# schematic.net
KiCad netlist of a schematic drawn in EAGLE
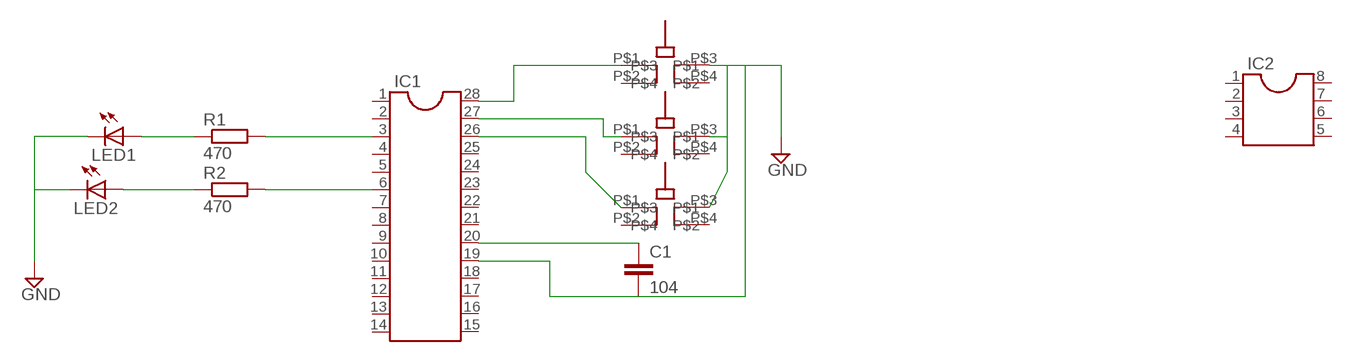
[diagram p0: schematic, sheet 1]

(export (version "E")
  (design (tool "Eeschema 10.0.6"))
  (components
    (comp (ref "C1")
      (value "104")
      (footprint "eagle-import:C2.5-5")
      (libsource (lib "eagle-import") (part "C2.5/5"))
    )
    (comp (ref "IC1")
      (value "DIL28-3")
      (footprint "eagle-import:DIL28-3")
      (libsource (lib "eagle-import") (part "DIL28-3"))
    )
    (comp (ref "IC2")
      (value "DIL8")
      (footprint "eagle-import:DIL08")
      (libsource (lib "eagle-import") (part "DIL8"))
    )
    (comp (ref "LED1")
      (value "LED3MM")
      (footprint "eagle-import:LED3MM")
      (libsource (lib "eagle-import") (part "LED3MM"))
    )
    (comp (ref "LED2")
      (value "LED3MM")
      (footprint "eagle-import:LED3MM")
      (libsource (lib "eagle-import") (part "LED3MM"))
    )
    (comp (ref "R1")
      (value "470")
      (footprint "eagle-import:0204_7")
      (libsource (lib "eagle-import") (part "R-EU_0204/7"))
    )
    (comp (ref "R2")
      (value "470")
      (footprint "eagle-import:0204_7")
      (libsource (lib "eagle-import") (part "R-EU_0204/7"))
    )
    (comp (ref "SW3")
      (value "KS4B")
      (footprint "eagle-import:KS4B")
      (libsource (lib "eagle-import") (part "KS4B"))
    )
    (comp (ref "U$1")
      (value "KS4B")
      (footprint "eagle-import:KS4B")
      (libsource (lib "eagle-import") (part "KS4B"))
    )
    (comp (ref "U$2")
      (value "KS4B")
      (footprint "eagle-import:KS4B")
      (libsource (lib "eagle-import") (part "KS4B"))
    )
  )
  (nets
    (net (code "1") (name "GND") (class "Default")
      (node (ref "C1") (pin "2") (pinfunction "2_2") (pintype "passive"))
      (node (ref "IC1") (pin "19") (pinfunction "19_19") (pintype "passive"))
      (node (ref "LED1") (pin "K") (pinfunction "C_K") (pintype "passive"))
      (node (ref "LED2") (pin "K") (pinfunction "C_K") (pintype "passive"))
      (node (ref "SW3") (pin "P$3") (pinfunction "P$3_P$3") (pintype "bidirectional"))
      (node (ref "U$1") (pin "P$3") (pinfunction "P$3_P$3") (pintype "bidirectional"))
      (node (ref "U$2") (pin "P$3") (pinfunction "P$3_P$3") (pintype "bidirectional"))
    )
    (net (code "2") (name "Net-(C1-Pad1)") (class "Default")
      (node (ref "C1") (pin "1") (pinfunction "1_1") (pintype "passive"))
      (node (ref "IC1") (pin "20") (pinfunction "20_20") (pintype "passive"))
    )
    (net (code "3") (name "Net-(IC1-Pad3)") (class "Default")
      (node (ref "IC1") (pin "3") (pinfunction "3_3") (pintype "passive"))
      (node (ref "R1") (pin "2") (pinfunction "2_2") (pintype "passive"))
    )
    (net (code "4") (name "Net-(IC1-Pad6)") (class "Default")
      (node (ref "IC1") (pin "6") (pinfunction "6_6") (pintype "passive"))
      (node (ref "R2") (pin "2") (pinfunction "2_2") (pintype "passive"))
    )
    (net (code "5") (name "Net-(IC1-Pad26)") (class "Default")
      (node (ref "IC1") (pin "26") (pinfunction "26_26") (pintype "passive"))
      (node (ref "SW3") (pin "P$1") (pinfunction "P$1_P$1") (pintype "bidirectional"))
    )
    (net (code "6") (name "Net-(IC1-Pad27)") (class "Default")
      (node (ref "IC1") (pin "27") (pinfunction "27_27") (pintype "passive"))
      (node (ref "U$2") (pin "P$1") (pinfunction "P$1_P$1") (pintype "bidirectional"))
    )
    (net (code "7") (name "Net-(IC1-Pad28)") (class "Default")
      (node (ref "IC1") (pin "28") (pinfunction "28_28") (pintype "passive"))
      (node (ref "U$1") (pin "P$1") (pinfunction "P$1_P$1") (pintype "bidirectional"))
    )
    (net (code "8") (name "Net-(LED1-PadA)") (class "Default")
      (node (ref "LED1") (pin "A") (pinfunction "A_A") (pintype "passive"))
      (node (ref "R1") (pin "1") (pinfunction "1_1") (pintype "passive"))
    )
    (net (code "9") (name "Net-(LED2-PadA)") (class "Default")
      (node (ref "LED2") (pin "A") (pinfunction "A_A") (pintype "passive"))
      (node (ref "R2") (pin "1") (pinfunction "1_1") (pintype "passive"))
    )
    (net (code "10") (name "unconnected-(IC1-Pad1)") (class "Default")
      (node (ref "IC1") (pin "1") (pinfunction "1_1") (pintype "passive"))
    )
    (net (code "11") (name "unconnected-(IC1-Pad2)") (class "Default")
      (node (ref "IC1") (pin "2") (pinfunction "2_2") (pintype "passive"))
    )
    (net (code "12") (name "unconnected-(IC1-Pad4)") (class "Default")
      (node (ref "IC1") (pin "4") (pinfunction "4_4") (pintype "passive"))
    )
    (net (code "13") (name "unconnected-(IC1-Pad5)") (class "Default")
      (node (ref "IC1") (pin "5") (pinfunction "5_5") (pintype "passive"))
    )
    (net (code "14") (name "unconnected-(IC1-Pad7)") (class "Default")
      (node (ref "IC1") (pin "7") (pinfunction "7_7") (pintype "passive"))
    )
    (net (code "15") (name "unconnected-(IC1-Pad8)") (class "Default")
      (node (ref "IC1") (pin "8") (pinfunction "8_8") (pintype "passive"))
    )
    (net (code "16") (name "unconnected-(IC1-Pad9)") (class "Default")
      (node (ref "IC1") (pin "9") (pinfunction "9_9") (pintype "passive"))
    )
    (net (code "17") (name "unconnected-(IC1-Pad10)") (class "Default")
      (node (ref "IC1") (pin "10") (pinfunction "10_10") (pintype "passive"))
    )
    (net (code "18") (name "unconnected-(IC1-Pad11)") (class "Default")
      (node (ref "IC1") (pin "11") (pinfunction "11_11") (pintype "passive"))
    )
    (net (code "19") (name "unconnected-(IC1-Pad12)") (class "Default")
      (node (ref "IC1") (pin "12") (pinfunction "12_12") (pintype "passive"))
    )
    (net (code "20") (name "unconnected-(IC1-Pad13)") (class "Default")
      (node (ref "IC1") (pin "13") (pinfunction "13_13") (pintype "passive"))
    )
    (net (code "21") (name "unconnected-(IC1-Pad14)") (class "Default")
      (node (ref "IC1") (pin "14") (pinfunction "14_14") (pintype "passive"))
    )
    (net (code "22") (name "unconnected-(IC1-Pad15)") (class "Default")
      (node (ref "IC1") (pin "15") (pinfunction "15_15") (pintype "passive"))
    )
    (net (code "23") (name "unconnected-(IC1-Pad16)") (class "Default")
      (node (ref "IC1") (pin "16") (pinfunction "16_16") (pintype "passive"))
    )
    (net (code "24") (name "unconnected-(IC1-Pad17)") (class "Default")
      (node (ref "IC1") (pin "17") (pinfunction "17_17") (pintype "passive"))
    )
    (net (code "25") (name "unconnected-(IC1-Pad18)") (class "Default")
      (node (ref "IC1") (pin "18") (pinfunction "18_18") (pintype "passive"))
    )
    (net (code "26") (name "unconnected-(IC1-Pad21)") (class "Default")
      (node (ref "IC1") (pin "21") (pinfunction "21_21") (pintype "passive"))
    )
    (net (code "27") (name "unconnected-(IC1-Pad22)") (class "Default")
      (node (ref "IC1") (pin "22") (pinfunction "22_22") (pintype "passive"))
    )
    (net (code "28") (name "unconnected-(IC1-Pad23)") (class "Default")
      (node (ref "IC1") (pin "23") (pinfunction "23_23") (pintype "passive"))
    )
    (net (code "29") (name "unconnected-(IC1-Pad24)") (class "Default")
      (node (ref "IC1") (pin "24") (pinfunction "24_24") (pintype "passive"))
    )
    (net (code "30") (name "unconnected-(IC1-Pad25)") (class "Default")
      (node (ref "IC1") (pin "25") (pinfunction "25_25") (pintype "passive"))
    )
    (net (code "31") (name "unconnected-(IC2-Pad1)") (class "Default")
      (node (ref "IC2") (pin "1") (pinfunction "1_1") (pintype "passive"))
    )
    (net (code "32") (name "unconnected-(IC2-Pad2)") (class "Default")
      (node (ref "IC2") (pin "2") (pinfunction "2_2") (pintype "passive"))
    )
    (net (code "33") (name "unconnected-(IC2-Pad3)") (class "Default")
      (node (ref "IC2") (pin "3") (pinfunction "3_3") (pintype "passive"))
    )
    (net (code "34") (name "unconnected-(IC2-Pad4)") (class "Default")
      (node (ref "IC2") (pin "4") (pinfunction "4_4") (pintype "passive"))
    )
    (net (code "35") (name "unconnected-(IC2-Pad5)") (class "Default")
      (node (ref "IC2") (pin "5") (pinfunction "5_5") (pintype "passive"))
    )
    (net (code "36") (name "unconnected-(IC2-Pad6)") (class "Default")
      (node (ref "IC2") (pin "6") (pinfunction "6_6") (pintype "passive"))
    )
    (net (code "37") (name "unconnected-(IC2-Pad7)") (class "Default")
      (node (ref "IC2") (pin "7") (pinfunction "7_7") (pintype "passive"))
    )
    (net (code "38") (name "unconnected-(IC2-Pad8)") (class "Default")
      (node (ref "IC2") (pin "8") (pinfunction "8_8") (pintype "passive"))
    )
    (net (code "39") (name "unconnected-(SW3-PadP$2)") (class "Default")
      (node (ref "SW3") (pin "P$2") (pinfunction "P$2_P$2") (pintype "bidirectional"))
    )
    (net (code "40") (name "unconnected-(SW3-PadP$4)") (class "Default")
      (node (ref "SW3") (pin "P$4") (pinfunction "P$4_P$4") (pintype "bidirectional"))
    )
    (net (code "41") (name "unconnected-(U$1-PadP$2)") (class "Default")
      (node (ref "U$1") (pin "P$2") (pinfunction "P$2_P$2") (pintype "bidirectional"))
    )
    (net (code "42") (name "unconnected-(U$1-PadP$4)") (class "Default")
      (node (ref "U$1") (pin "P$4") (pinfunction "P$4_P$4") (pintype "bidirectional"))
    )
    (net (code "43") (name "unconnected-(U$2-PadP$2)") (class "Default")
      (node (ref "U$2") (pin "P$2") (pinfunction "P$2_P$2") (pintype "bidirectional"))
    )
    (net (code "44") (name "unconnected-(U$2-PadP$4)") (class "Default")
      (node (ref "U$2") (pin "P$4") (pinfunction "P$4_P$4") (pintype "bidirectional"))
    )
  )
)
